# NIRGM_V7.net
KiCad netlist of a schematic drawn in EAGLE
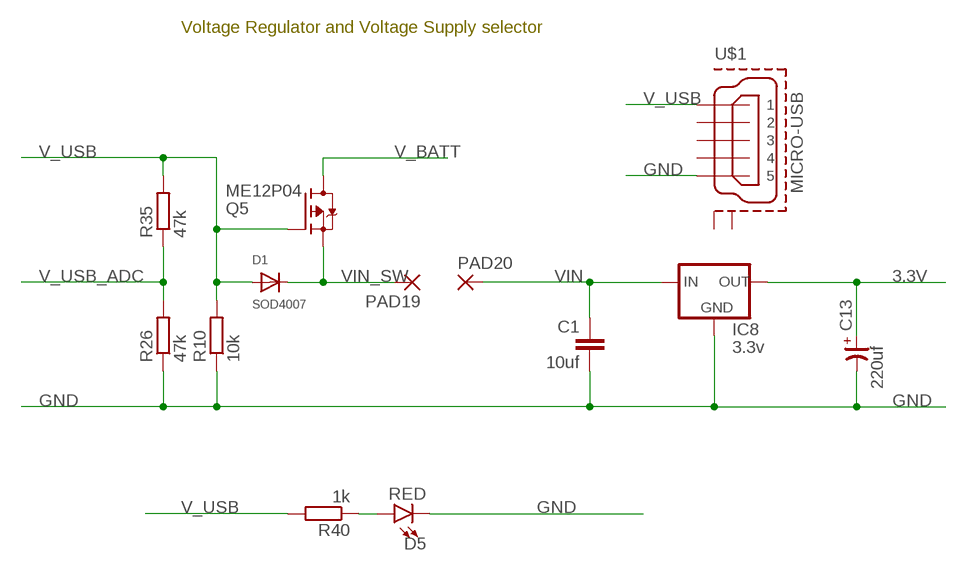
[diagram p0: schematic, sheet 1]
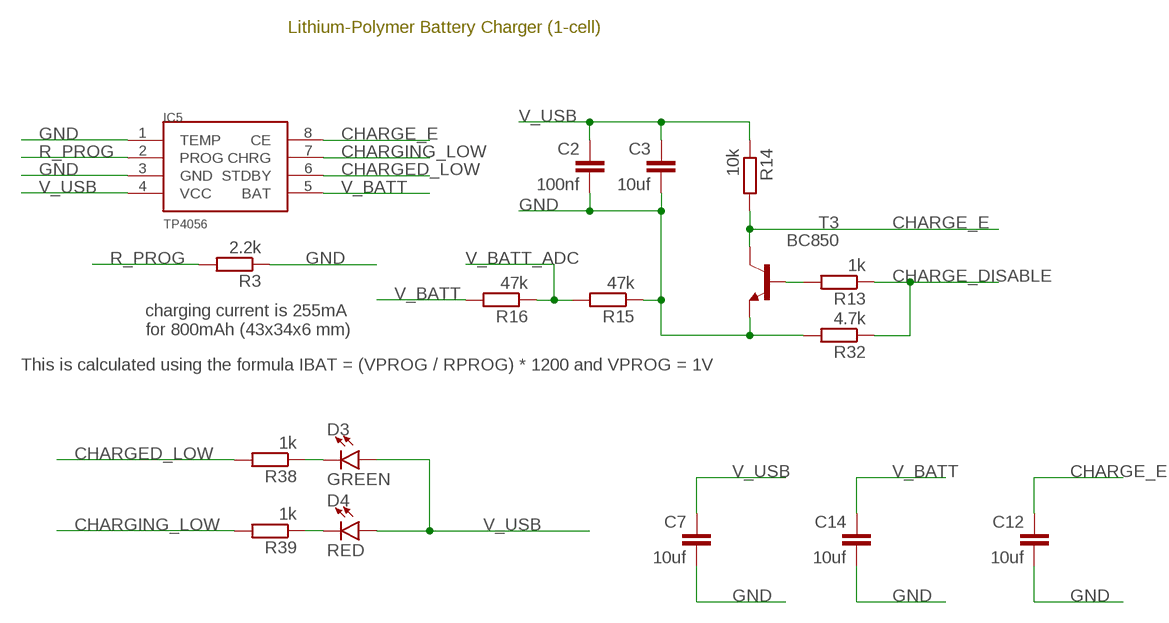
[diagram p1: schematic, sheet 2]
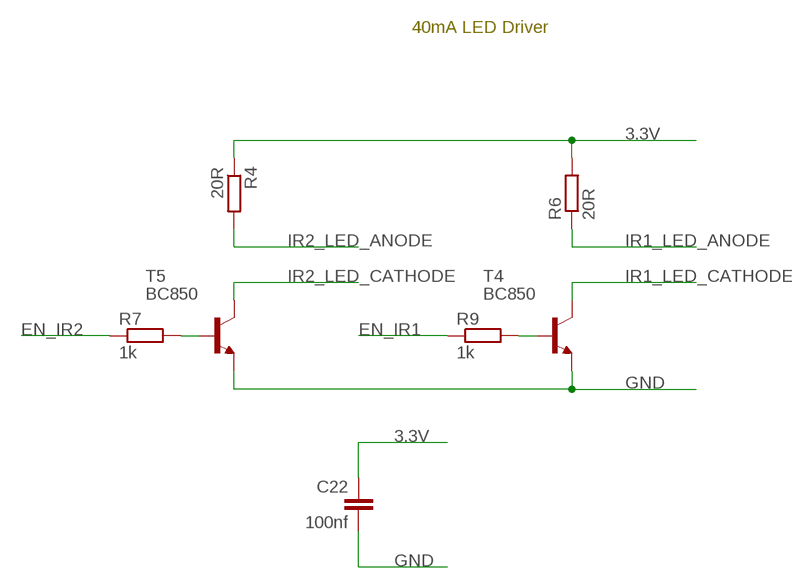
[diagram p2: schematic, sheet 3]
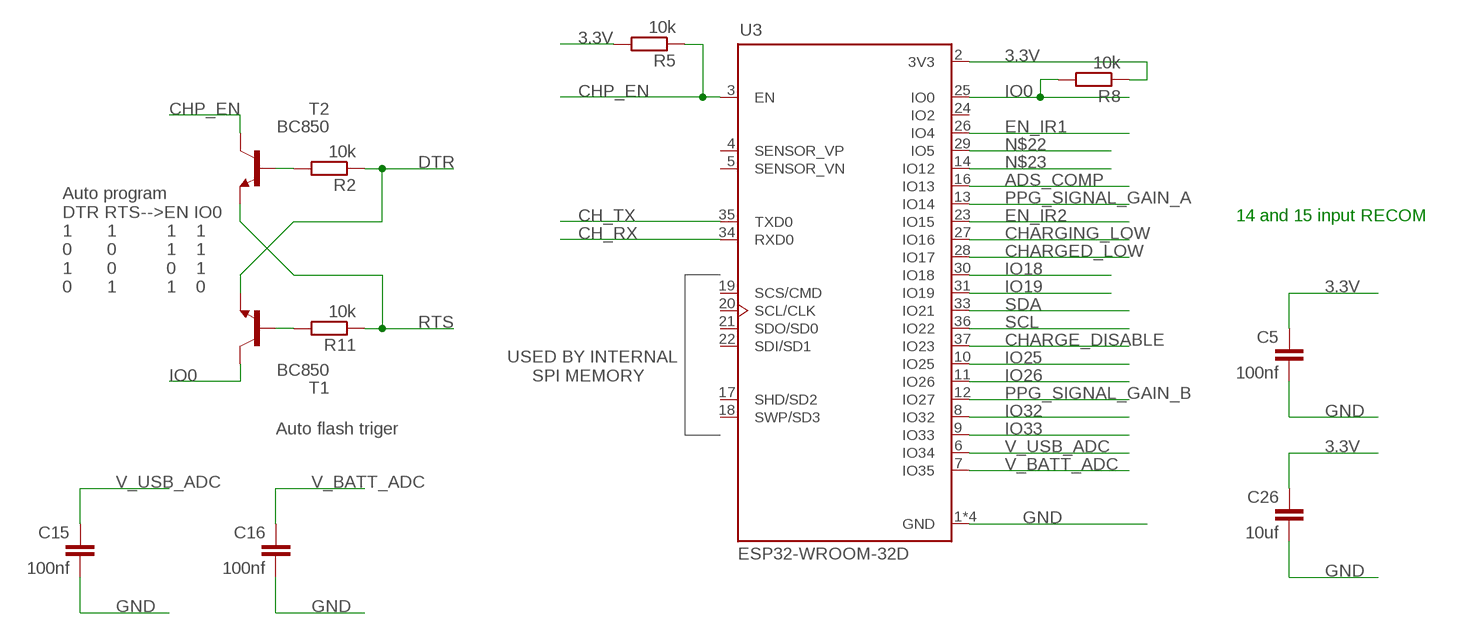
[diagram p3: schematic, sheet 4]
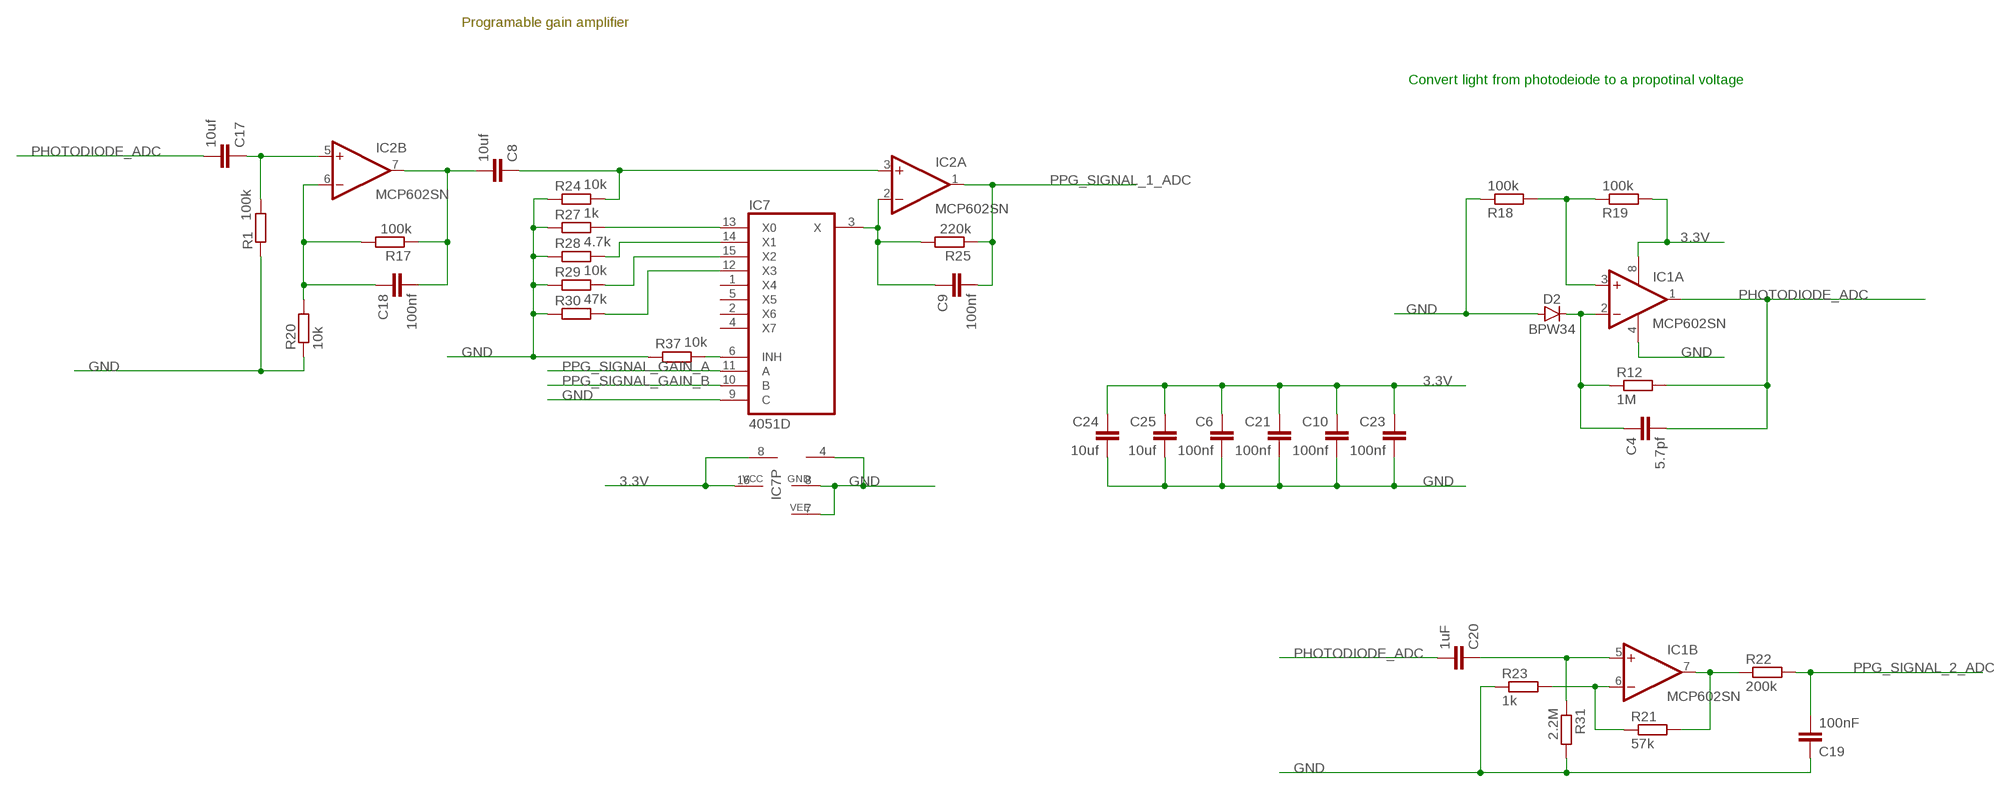
[diagram p4: schematic, sheet 5]
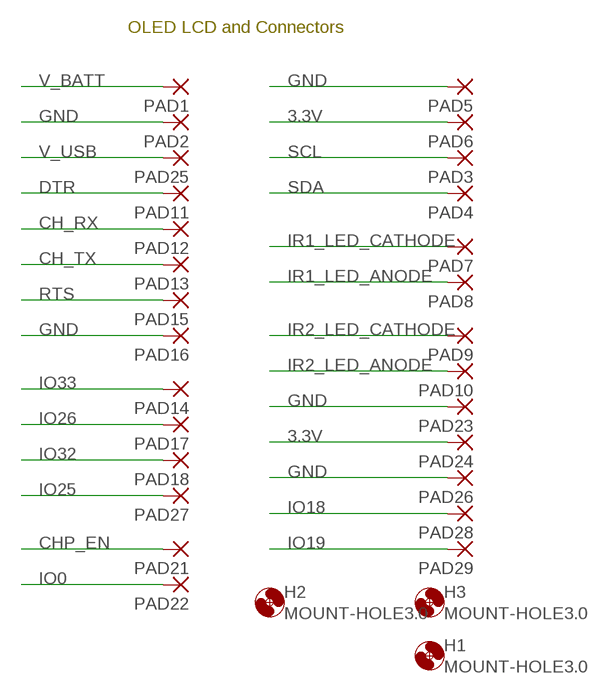
[diagram p5: schematic, sheet 6]
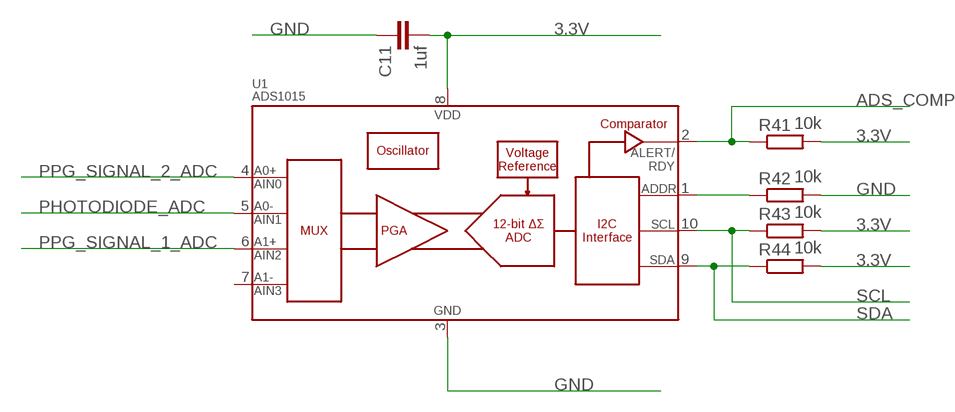
[diagram p6: schematic, sheet 7]

(export (version "E")
  (design (tool "Eeschema 10.0.6"))
  (components
    (comp (ref "H1")
      (value "MOUNT-HOLE3.0")
      (footprint "eagle-import:3,0")
      (libsource (lib "eagle-import") (part "MOUNT-HOLE3.0"))
    )
    (comp (ref "H2")
      (value "MOUNT-HOLE3.0")
      (footprint "eagle-import:3,0")
      (libsource (lib "eagle-import") (part "MOUNT-HOLE3.0"))
    )
    (comp (ref "H3")
      (value "MOUNT-HOLE3.0")
      (footprint "eagle-import:3,0")
      (libsource (lib "eagle-import") (part "MOUNT-HOLE3.0"))
    )
    (comp (ref "PAD1")
      (value "WIREPADSMD5-2,5")
      (footprint "eagle-import:5-2,5")
      (libsource (lib "eagle-import") (part "WIREPADSMD5-2,5"))
    )
    (comp (ref "PAD2")
      (value "WIREPADSMD5-2,5")
      (footprint "eagle-import:5-2,5")
      (libsource (lib "eagle-import") (part "WIREPADSMD5-2,5"))
    )
    (comp (ref "PAD3")
      (value "SMD2")
      (footprint "eagle-import:SMD1,27-2,54")
      (libsource (lib "eagle-import") (part "SMD2"))
    )
    (comp (ref "PAD4")
      (value "SMD2")
      (footprint "eagle-import:SMD1,27-2,54")
      (libsource (lib "eagle-import") (part "SMD2"))
    )
    (comp (ref "PAD5")
      (value "SMD2")
      (footprint "eagle-import:SMD1,27-2,54")
      (libsource (lib "eagle-import") (part "SMD2"))
    )
    (comp (ref "PAD6")
      (value "SMD2")
      (footprint "eagle-import:SMD1,27-2,54")
      (libsource (lib "eagle-import") (part "SMD2"))
    )
    (comp (ref "PAD7")
      (value "SMD2")
      (footprint "eagle-import:SMD1,27-2,54")
      (libsource (lib "eagle-import") (part "SMD2"))
    )
    (comp (ref "PAD8")
      (value "SMD2")
      (footprint "eagle-import:SMD1,27-2,54")
      (libsource (lib "eagle-import") (part "SMD2"))
    )
    (comp (ref "PAD9")
      (value "SMD2")
      (footprint "eagle-import:SMD1,27-2,54")
      (libsource (lib "eagle-import") (part "SMD2"))
    )
    (comp (ref "PAD10")
      (value "SMD2")
      (footprint "eagle-import:SMD1,27-2,54")
      (libsource (lib "eagle-import") (part "SMD2"))
    )
    (comp (ref "PAD11")
      (value "SMD2")
      (footprint "eagle-import:SMD1,27-2,54")
      (libsource (lib "eagle-import") (part "SMD2"))
    )
    (comp (ref "PAD12")
      (value "SMD2")
      (footprint "eagle-import:SMD1,27-2,54")
      (libsource (lib "eagle-import") (part "SMD2"))
    )
    (comp (ref "PAD13")
      (value "SMD2")
      (footprint "eagle-import:SMD1,27-2,54")
      (libsource (lib "eagle-import") (part "SMD2"))
    )
    (comp (ref "PAD14")
      (value "SMD2")
      (footprint "eagle-import:SMD1,27-2,54")
      (libsource (lib "eagle-import") (part "SMD2"))
    )
    (comp (ref "PAD15")
      (value "SMD2")
      (footprint "eagle-import:SMD1,27-2,54")
      (libsource (lib "eagle-import") (part "SMD2"))
    )
    (comp (ref "PAD16")
      (value "SMD2")
      (footprint "eagle-import:SMD1,27-2,54")
      (libsource (lib "eagle-import") (part "SMD2"))
    )
    (comp (ref "PAD17")
      (value "SMD2")
      (footprint "eagle-import:SMD1,27-2,54")
      (libsource (lib "eagle-import") (part "SMD2"))
    )
    (comp (ref "PAD18")
      (value "SMD2")
      (footprint "eagle-import:SMD1,27-2,54")
      (libsource (lib "eagle-import") (part "SMD2"))
    )
    (comp (ref "PAD21")
      (value "SMD2")
      (footprint "eagle-import:SMD1,27-2,54")
      (libsource (lib "eagle-import") (part "SMD2"))
    )
    (comp (ref "PAD22")
      (value "SMD2")
      (footprint "eagle-import:SMD1,27-2,54")
      (libsource (lib "eagle-import") (part "SMD2"))
    )
    (comp (ref "PAD23")
      (value "SMD2")
      (footprint "eagle-import:SMD1,27-2,54")
      (libsource (lib "eagle-import") (part "SMD2"))
    )
    (comp (ref "PAD24")
      (value "SMD2")
      (footprint "eagle-import:SMD1,27-2,54")
      (libsource (lib "eagle-import") (part "SMD2"))
    )
    (comp (ref "PAD25")
      (value "SMD2")
      (footprint "eagle-import:SMD1,27-2,54")
      (libsource (lib "eagle-import") (part "SMD2"))
    )
    (comp (ref "PAD26")
      (value "SMD2")
      (footprint "eagle-import:SMD1,27-2,54")
      (libsource (lib "eagle-import") (part "SMD2"))
    )
    (comp (ref "PAD27")
      (value "SMD2")
      (footprint "eagle-import:SMD1,27-2,54")
      (libsource (lib "eagle-import") (part "SMD2"))
    )
    (comp (ref "PAD28")
      (value "SMD2")
      (footprint "eagle-import:SMD1,27-2,54")
      (libsource (lib "eagle-import") (part "SMD2"))
    )
    (comp (ref "PAD29")
      (value "SMD2")
      (footprint "eagle-import:SMD1,27-2,54")
      (libsource (lib "eagle-import") (part "SMD2"))
    )
    (comp (ref "C2")
      (value "100nf")
      (footprint "eagle-import:C1206K")
      (libsource (lib "eagle-import") (part "C-EUC1206K"))
    )
    (comp (ref "C3")
      (value "10uf")
      (footprint "eagle-import:C1206K")
      (libsource (lib "eagle-import") (part "C-EUC1206K"))
    )
    (comp (ref "C7")
      (value "10uf")
      (footprint "eagle-import:C1206K")
      (libsource (lib "eagle-import") (part "C-EUC1206K"))
    )
    (comp (ref "C12")
      (value "10uf")
      (footprint "eagle-import:C1206K")
      (libsource (lib "eagle-import") (part "C-EUC1206K"))
    )
    (comp (ref "C14")
      (value "10uf")
      (footprint "eagle-import:C1206K")
      (libsource (lib "eagle-import") (part "C-EUC1206K"))
    )
    (comp (ref "D3")
      (value "GREEN")
      (footprint "eagle-import:LED-1206")
      (libsource (lib "eagle-import") (part "LED-GREEN1206"))
    )
    (comp (ref "D4")
      (value "RED")
      (footprint "eagle-import:LED-1206")
      (libsource (lib "eagle-import") (part "LED-GREEN1206"))
    )
    (comp (ref "IC5")
      (value "TP4056")
      (footprint "eagle-import:SOP-8")
      (libsource (lib "eagle-import") (part "TP4056"))
    )
    (comp (ref "R3")
      (value "2.2k")
      (footprint "eagle-import:R1206")
      (libsource (lib "eagle-import") (part "R-EU_R1206"))
    )
    (comp (ref "R13")
      (value "1k")
      (footprint "eagle-import:R1206")
      (libsource (lib "eagle-import") (part "R-EU_R1206"))
    )
    (comp (ref "R14")
      (value "10k")
      (footprint "eagle-import:R1206")
      (libsource (lib "eagle-import") (part "R-EU_R1206"))
    )
    (comp (ref "R15")
      (value "47k")
      (footprint "eagle-import:R1206")
      (libsource (lib "eagle-import") (part "R-EU_R1206"))
    )
    (comp (ref "R16")
      (value "47k")
      (footprint "eagle-import:R1206")
      (libsource (lib "eagle-import") (part "R-EU_R1206"))
    )
    (comp (ref "R32")
      (value "4.7k")
      (footprint "eagle-import:R1206")
      (libsource (lib "eagle-import") (part "R-EU_R1206"))
    )
    (comp (ref "R38")
      (value "1k")
      (footprint "eagle-import:R1206")
      (libsource (lib "eagle-import") (part "R-EU_R1206"))
    )
    (comp (ref "R39")
      (value "1k")
      (footprint "eagle-import:R1206")
      (libsource (lib "eagle-import") (part "R-EU_R1206"))
    )
    (comp (ref "T3")
      (value "BC850")
      (footprint "eagle-import:SOT23")
      (libsource (lib "eagle-import") (part "BC850"))
    )
    (comp (ref "C11")
      (value "1uf")
      (footprint "eagle-import:C1206K")
      (libsource (lib "eagle-import") (part "C-EUC1206K"))
    )
    (comp (ref "R41")
      (value "10k")
      (footprint "eagle-import:R1206")
      (libsource (lib "eagle-import") (part "R-EU_R1206"))
    )
    (comp (ref "R42")
      (value "10k")
      (footprint "eagle-import:R1206")
      (libsource (lib "eagle-import") (part "R-EU_R1206"))
    )
    (comp (ref "R43")
      (value "10k")
      (footprint "eagle-import:R1206")
      (libsource (lib "eagle-import") (part "R-EU_R1206"))
    )
    (comp (ref "R44")
      (value "10k")
      (footprint "eagle-import:R1206")
      (libsource (lib "eagle-import") (part "R-EU_R1206"))
    )
    (comp (ref "U1")
      (value "ADS1015")
      (footprint "eagle-import:MSOP10")
      (libsource (lib "eagle-import") (part "ADS1015"))
    )
    (comp (ref "C1")
      (value "10uf")
      (footprint "eagle-import:C1206K")
      (libsource (lib "eagle-import") (part "C-EUC1206K"))
    )
    (comp (ref "C13")
      (value "220uf")
      (footprint "eagle-import:7343_T")
      (libsource (lib "eagle-import") (part "CP-7343"))
    )
    (comp (ref "D1")
      (value "SOD4007")
      (footprint "eagle-import:SOD-123FL")
      (libsource (lib "eagle-import") (part "DIODE_SOD-123FL"))
    )
    (comp (ref "D5")
      (value "RED")
      (footprint "eagle-import:LED-1206")
      (libsource (lib "eagle-import") (part "LED-GREEN1206"))
    )
    (comp (ref "IC8")
      (value "3.3v")
      (footprint "eagle-import:TO252")
      (libsource (lib "eagle-import") (part "LM1117TO252"))
    )
    (comp (ref "PAD19")
      (value "SMD2")
      (footprint "eagle-import:SMD1,27-2,54")
      (libsource (lib "eagle-import") (part "SMD2"))
    )
    (comp (ref "PAD20")
      (value "SMD2")
      (footprint "eagle-import:SMD1,27-2,54")
      (libsource (lib "eagle-import") (part "SMD2"))
    )
    (comp (ref "Q5")
      (value "ME12P04")
      (footprint "eagle-import:TO252")
      (libsource (lib "eagle-import") (part "FDD4141TO252"))
    )
    (comp (ref "R10")
      (value "10k")
      (footprint "eagle-import:R1206")
      (libsource (lib "eagle-import") (part "R-EU_R1206"))
    )
    (comp (ref "R26")
      (value "47k")
      (footprint "eagle-import:R1206")
      (libsource (lib "eagle-import") (part "R-EU_R1206"))
    )
    (comp (ref "R35")
      (value "47k")
      (footprint "eagle-import:R1206")
      (libsource (lib "eagle-import") (part "R-EU_R1206"))
    )
    (comp (ref "R40")
      (value "1k")
      (footprint "eagle-import:R1206")
      (libsource (lib "eagle-import") (part "R-EU_R1206"))
    )
    (comp (ref "U$1")
      (value "MICRO-USB")
      (footprint "eagle-import:47589-0001")
      (libsource (lib "eagle-import") (part "MICRO-USB-RECEPTACLE47589-0001"))
    )
    (comp (ref "C22")
      (value "100nf")
      (footprint "eagle-import:C1206K")
      (libsource (lib "eagle-import") (part "C-EUC1206K"))
    )
    (comp (ref "R4")
      (value "20R")
      (footprint "eagle-import:R1206")
      (libsource (lib "eagle-import") (part "R-EU_R1206"))
    )
    (comp (ref "R6")
      (value "20R")
      (footprint "eagle-import:R1206")
      (libsource (lib "eagle-import") (part "R-EU_R1206"))
    )
    (comp (ref "R7")
      (value "1k")
      (footprint "eagle-import:R1206")
      (libsource (lib "eagle-import") (part "R-EU_R1206"))
    )
    (comp (ref "R9")
      (value "1k")
      (footprint "eagle-import:R1206")
      (libsource (lib "eagle-import") (part "R-EU_R1206"))
    )
    (comp (ref "T4")
      (value "BC850")
      (footprint "eagle-import:SOT23")
      (libsource (lib "eagle-import") (part "BC850"))
    )
    (comp (ref "T5")
      (value "BC850")
      (footprint "eagle-import:SOT23")
      (libsource (lib "eagle-import") (part "BC850"))
    )
    (comp (ref "C5")
      (value "100nf")
      (footprint "eagle-import:C1206K")
      (libsource (lib "eagle-import") (part "C-EUC1206K"))
    )
    (comp (ref "C15")
      (value "100nf")
      (footprint "eagle-import:C1206K")
      (libsource (lib "eagle-import") (part "C-EUC1206K"))
    )
    (comp (ref "C16")
      (value "100nf")
      (footprint "eagle-import:C1206K")
      (libsource (lib "eagle-import") (part "C-EUC1206K"))
    )
    (comp (ref "C26")
      (value "10uf")
      (footprint "eagle-import:C1206K")
      (libsource (lib "eagle-import") (part "C-EUC1206K"))
    )
    (comp (ref "R2")
      (value "10k")
      (footprint "eagle-import:R1206")
      (libsource (lib "eagle-import") (part "R-EU_R1206"))
    )
    (comp (ref "R5")
      (value "10k")
      (footprint "eagle-import:R1206")
      (libsource (lib "eagle-import") (part "R-EU_R1206"))
    )
    (comp (ref "R8")
      (value "10k")
      (footprint "eagle-import:R1206")
      (libsource (lib "eagle-import") (part "R-EU_R1206"))
    )
    (comp (ref "R11")
      (value "10k")
      (footprint "eagle-import:R1206")
      (libsource (lib "eagle-import") (part "R-EU_R1206"))
    )
    (comp (ref "T1")
      (value "BC850")
      (footprint "eagle-import:SOT23")
      (libsource (lib "eagle-import") (part "BC850"))
    )
    (comp (ref "T2")
      (value "BC850")
      (footprint "eagle-import:SOT23")
      (libsource (lib "eagle-import") (part "BC850"))
    )
    (comp (ref "U3")
      (value "ESP32-WROOM-32D")
      (footprint "eagle-import:MODULE_ESP32-WROOM-32D")
      (fields (field (name "MF") "Espressif Systems"))
      (libsource (lib "eagle-import") (part "ESP32-WROOM-32D"))
    )
    (comp (ref "C4")
      (value "5.7pf")
      (footprint "eagle-import:C1206K")
      (libsource (lib "eagle-import") (part "C-EUC1206K"))
    )
    (comp (ref "C6")
      (value "100nf")
      (footprint "eagle-import:C1206K")
      (libsource (lib "eagle-import") (part "C-EUC1206K"))
    )
    (comp (ref "C8")
      (value "10uf")
      (footprint "eagle-import:C1206K")
      (libsource (lib "eagle-import") (part "C-EUC1206K"))
    )
    (comp (ref "C9")
      (value "100nf")
      (footprint "eagle-import:C1206K")
      (libsource (lib "eagle-import") (part "C-EUC1206K"))
    )
    (comp (ref "C10")
      (value "100nf")
      (footprint "eagle-import:C1206K")
      (libsource (lib "eagle-import") (part "C-EUC1206K"))
    )
    (comp (ref "C17")
      (value "10uf")
      (footprint "eagle-import:C1206K")
      (libsource (lib "eagle-import") (part "C-EUC1206K"))
    )
    (comp (ref "C18")
      (value "100nf")
      (footprint "eagle-import:C1206K")
      (libsource (lib "eagle-import") (part "C-EUC1206K"))
    )
    (comp (ref "C19")
      (value "100nF")
      (footprint "eagle-import:C1206K")
      (libsource (lib "eagle-import") (part "C-EUC1206K"))
    )
    (comp (ref "C20")
      (value "1uF")
      (footprint "eagle-import:C1206K")
      (libsource (lib "eagle-import") (part "C-EUC1206K"))
    )
    (comp (ref "C21")
      (value "100nf")
      (footprint "eagle-import:C1206K")
      (libsource (lib "eagle-import") (part "C-EUC1206K"))
    )
    (comp (ref "C23")
      (value "100nf")
      (footprint "eagle-import:C1206K")
      (libsource (lib "eagle-import") (part "C-EUC1206K"))
    )
    (comp (ref "C24")
      (value "10uf")
      (footprint "eagle-import:C1206K")
      (libsource (lib "eagle-import") (part "C-EUC1206K"))
    )
    (comp (ref "C25")
      (value "10uf")
      (footprint "eagle-import:C1206K")
      (libsource (lib "eagle-import") (part "C-EUC1206K"))
    )
    (comp (ref "D2")
      (value "BPW34")
      (footprint "eagle-import:BPW34")
      (libsource (lib "eagle-import") (part "BPW34"))
    )
    (comp (ref "IC1")
      (value "MCP602SN")
      (footprint "eagle-import:SO08")
      (libsource (lib "eagle-import") (part "linear_262_MCP602SN"))
    )
    (comp (ref "IC2")
      (value "MCP602SN")
      (footprint "eagle-import:SO08")
      (libsource (lib "eagle-import") (part "MCP602SN"))
    )
    (comp (ref "IC7")
      (value "4051D")
      (footprint "eagle-import:SO16")
      (libsource (lib "eagle-import") (part "4051D"))
    )
    (comp (ref "R1")
      (value "100k")
      (footprint "eagle-import:R1206")
      (libsource (lib "eagle-import") (part "R-EU_R1206"))
    )
    (comp (ref "R12")
      (value "1M")
      (footprint "eagle-import:R1206")
      (libsource (lib "eagle-import") (part "R-EU_R1206"))
    )
    (comp (ref "R17")
      (value "100k")
      (footprint "eagle-import:R1206")
      (libsource (lib "eagle-import") (part "R-EU_R1206"))
    )
    (comp (ref "R18")
      (value "100k")
      (footprint "eagle-import:R1206")
      (libsource (lib "eagle-import") (part "R-EU_R1206"))
    )
    (comp (ref "R19")
      (value "100k")
      (footprint "eagle-import:R1206")
      (libsource (lib "eagle-import") (part "R-EU_R1206"))
    )
    (comp (ref "R20")
      (value "10k")
      (footprint "eagle-import:R1206")
      (libsource (lib "eagle-import") (part "R-EU_R1206"))
    )
    (comp (ref "R21")
      (value "57k")
      (footprint "eagle-import:R1206")
      (libsource (lib "eagle-import") (part "R-EU_R1206"))
    )
    (comp (ref "R22")
      (value "200k")
      (footprint "eagle-import:R1206")
      (libsource (lib "eagle-import") (part "R-EU_R1206"))
    )
    (comp (ref "R23")
      (value "1k")
      (footprint "eagle-import:R1206")
      (libsource (lib "eagle-import") (part "R-EU_R1206"))
    )
    (comp (ref "R24")
      (value "10k")
      (footprint "eagle-import:R1206")
      (libsource (lib "eagle-import") (part "R-EU_R1206"))
    )
    (comp (ref "R25")
      (value "220k")
      (footprint "eagle-import:R1206")
      (libsource (lib "eagle-import") (part "R-EU_R1206"))
    )
    (comp (ref "R27")
      (value "1k")
      (footprint "eagle-import:R1206")
      (libsource (lib "eagle-import") (part "R-EU_R1206"))
    )
    (comp (ref "R28")
      (value "4.7k")
      (footprint "eagle-import:R1206")
      (libsource (lib "eagle-import") (part "R-EU_R1206"))
    )
    (comp (ref "R29")
      (value "10k")
      (footprint "eagle-import:R1206")
      (libsource (lib "eagle-import") (part "R-EU_R1206"))
    )
    (comp (ref "R30")
      (value "47k")
      (footprint "eagle-import:R1206")
      (libsource (lib "eagle-import") (part "R-EU_R1206"))
    )
    (comp (ref "R31")
      (value "2.2M")
      (footprint "eagle-import:R1206")
      (libsource (lib "eagle-import") (part "R-EU_R1206"))
    )
    (comp (ref "R37")
      (value "10k")
      (footprint "eagle-import:R1206")
      (libsource (lib "eagle-import") (part "R-EU_R1206"))
    )
  )
  (nets
    (net (code "1") (name "3.3V") (class "Default")
      (node (ref "C10") (pin "1") (pinfunction "1_1") (pintype "passive"))
      (node (ref "C11") (pin "2") (pinfunction "2_2") (pintype "passive"))
      (node (ref "C13") (pin "+") (pinfunction "+_+") (pintype "passive"))
      (node (ref "C21") (pin "1") (pinfunction "1_1") (pintype "passive"))
      (node (ref "C22") (pin "1") (pinfunction "1_1") (pintype "passive"))
      (node (ref "C23") (pin "1") (pinfunction "1_1") (pintype "passive"))
      (node (ref "C24") (pin "1") (pinfunction "1_1") (pintype "passive"))
      (node (ref "C25") (pin "1") (pinfunction "1_1") (pintype "passive"))
      (node (ref "C26") (pin "1") (pinfunction "1_1") (pintype "passive"))
      (node (ref "C5") (pin "1") (pinfunction "1_1") (pintype "passive"))
      (node (ref "C6") (pin "1") (pinfunction "1_1") (pintype "passive"))
      (node (ref "IC1") (pin "8") (pinfunction "V+_8") (pintype "power_in"))
      (node (ref "IC2") (pin "8") (pinfunction "V+_8") (pintype "power_in"))
      (node (ref "IC7") (pin "16") (pinfunction "VCC_16") (pintype "power_in"))
      (node (ref "IC8") (pin "3") (pinfunction "OUT_3") (pintype "passive"))
      (node (ref "PAD24") (pin "1") (pinfunction "P_1") (pintype "passive"))
      (node (ref "PAD6") (pin "1") (pinfunction "P_1") (pintype "passive"))
      (node (ref "R19") (pin "2") (pinfunction "2_2") (pintype "passive"))
      (node (ref "R4") (pin "1") (pinfunction "1_1") (pintype "passive"))
      (node (ref "R41") (pin "2") (pinfunction "2_2") (pintype "passive"))
      (node (ref "R43") (pin "2") (pinfunction "2_2") (pintype "passive"))
      (node (ref "R44") (pin "2") (pinfunction "2_2") (pintype "passive"))
      (node (ref "R5") (pin "2") (pinfunction "2_2") (pintype "passive"))
      (node (ref "R6") (pin "2") (pinfunction "2_2") (pintype "passive"))
      (node (ref "R8") (pin "1") (pinfunction "1_1") (pintype "passive"))
      (node (ref "U1") (pin "8") (pinfunction "VDD_8") (pintype "bidirectional"))
      (node (ref "U3") (pin "2") (pinfunction "3V3_2") (pintype "power_in"))
    )
    (net (code "2") (name "ADS_COMP") (class "Default")
      (node (ref "R41") (pin "1") (pinfunction "1_1") (pintype "passive"))
      (node (ref "U1") (pin "2") (pinfunction "ALERT/RDY_2") (pintype "bidirectional"))
      (node (ref "U3") (pin "16") (pinfunction "IO13_16") (pintype "bidirectional"))
    )
    (net (code "3") (name "CHARGED_LOW") (class "Default")
      (node (ref "IC5") (pin "6") (pinfunction "STDBY_6") (pintype "bidirectional"))
      (node (ref "R38") (pin "2") (pinfunction "2_2") (pintype "passive"))
      (node (ref "U3") (pin "28") (pinfunction "IO17_28") (pintype "bidirectional"))
    )
    (net (code "4") (name "CHARGE_DISABLE") (class "Default")
      (node (ref "R13") (pin "1") (pinfunction "1_1") (pintype "passive"))
      (node (ref "R32") (pin "1") (pinfunction "1_1") (pintype "passive"))
      (node (ref "U3") (pin "37") (pinfunction "IO23_37") (pintype "bidirectional"))
    )
    (net (code "5") (name "CHARGE_E") (class "Default")
      (node (ref "C12") (pin "1") (pinfunction "1_1") (pintype "passive"))
      (node (ref "IC5") (pin "8") (pinfunction "CE_8") (pintype "bidirectional"))
      (node (ref "R14") (pin "2") (pinfunction "2_2") (pintype "passive"))
      (node (ref "T3") (pin "3") (pinfunction "C_3") (pintype "passive"))
    )
    (net (code "6") (name "CHARGING_LOW") (class "Default")
      (node (ref "IC5") (pin "7") (pinfunction "CHRG_7") (pintype "bidirectional"))
      (node (ref "R39") (pin "2") (pinfunction "2_2") (pintype "passive"))
      (node (ref "U3") (pin "27") (pinfunction "IO16_27") (pintype "bidirectional"))
    )
    (net (code "7") (name "CHP_EN") (class "Default")
      (node (ref "PAD21") (pin "1") (pinfunction "P_1") (pintype "passive"))
      (node (ref "R5") (pin "1") (pinfunction "1_1") (pintype "passive"))
      (node (ref "T2") (pin "3") (pinfunction "C_3") (pintype "passive"))
      (node (ref "U3") (pin "3") (pinfunction "EN_3") (pintype "input"))
    )
    (net (code "8") (name "CH_RX") (class "Default")
      (node (ref "PAD12") (pin "1") (pinfunction "P_1") (pintype "passive"))
      (node (ref "U3") (pin "34") (pinfunction "RXD0_34") (pintype "bidirectional"))
    )
    (net (code "9") (name "CH_TX") (class "Default")
      (node (ref "PAD13") (pin "1") (pinfunction "P_1") (pintype "passive"))
      (node (ref "U3") (pin "35") (pinfunction "TXD0_35") (pintype "bidirectional"))
    )
    (net (code "10") (name "DTR") (class "Default")
      (node (ref "PAD11") (pin "1") (pinfunction "P_1") (pintype "passive"))
      (node (ref "R2") (pin "1") (pinfunction "1_1") (pintype "passive"))
      (node (ref "T1") (pin "2") (pinfunction "E_2") (pintype "passive"))
    )
    (net (code "11") (name "EN_IR1") (class "Default")
      (node (ref "R9") (pin "1") (pinfunction "1_1") (pintype "passive"))
      (node (ref "U3") (pin "26") (pinfunction "IO4_26") (pintype "bidirectional"))
    )
    (net (code "12") (name "EN_IR2") (class "Default")
      (node (ref "R7") (pin "1") (pinfunction "1_1") (pintype "passive"))
      (node (ref "U3") (pin "23") (pinfunction "IO15_23") (pintype "bidirectional"))
    )
    (net (code "13") (name "GND") (class "Default")
      (node (ref "C1") (pin "2") (pinfunction "2_2") (pintype "passive"))
      (node (ref "C10") (pin "2") (pinfunction "2_2") (pintype "passive"))
      (node (ref "C11") (pin "1") (pinfunction "1_1") (pintype "passive"))
      (node (ref "C12") (pin "2") (pinfunction "2_2") (pintype "passive"))
      (node (ref "C13") (pin "-") (pinfunction "-_-") (pintype "passive"))
      (node (ref "C14") (pin "2") (pinfunction "2_2") (pintype "passive"))
      (node (ref "C15") (pin "2") (pinfunction "2_2") (pintype "passive"))
      (node (ref "C16") (pin "2") (pinfunction "2_2") (pintype "passive"))
      (node (ref "C19") (pin "1") (pinfunction "1_1") (pintype "passive"))
      (node (ref "C2") (pin "2") (pinfunction "2_2") (pintype "passive"))
      (node (ref "C21") (pin "2") (pinfunction "2_2") (pintype "passive"))
      (node (ref "C22") (pin "2") (pinfunction "2_2") (pintype "passive"))
      (node (ref "C23") (pin "2") (pinfunction "2_2") (pintype "passive"))
      (node (ref "C24") (pin "2") (pinfunction "2_2") (pintype "passive"))
      (node (ref "C25") (pin "2") (pinfunction "2_2") (pintype "passive"))
      (node (ref "C26") (pin "2") (pinfunction "2_2") (pintype "passive"))
      (node (ref "C3") (pin "2") (pinfunction "2_2") (pintype "passive"))
      (node (ref "C5") (pin "2") (pinfunction "2_2") (pintype "passive"))
      (node (ref "C6") (pin "2") (pinfunction "2_2") (pintype "passive"))
      (node (ref "C7") (pin "2") (pinfunction "2_2") (pintype "passive"))
      (node (ref "D2") (pin "P$1") (pinfunction "A_P$1") (pintype "passive"))
      (node (ref "D5") (pin "C") (pinfunction "C_C") (pintype "passive"))
      (node (ref "IC1") (pin "4") (pinfunction "V-_4") (pintype "power_in"))
      (node (ref "IC2") (pin "4") (pinfunction "V-_4") (pintype "power_in"))
      (node (ref "IC5") (pin "1") (pinfunction "TEMP_1") (pintype "bidirectional"))
      (node (ref "IC5") (pin "3") (pinfunction "GND_3") (pintype "bidirectional"))
      (node (ref "IC7") (pin "7") (pinfunction "VEE_7") (pintype "power_in"))
      (node (ref "IC7") (pin "8") (pinfunction "GND_8") (pintype "power_in"))
      (node (ref "IC7") (pin "9") (pinfunction "C_9") (pintype "input"))
      (node (ref "IC8") (pin "1") (pinfunction "GND_1") (pintype "input"))
      (node (ref "PAD16") (pin "1") (pinfunction "P_1") (pintype "passive"))
      (node (ref "PAD2") (pin "1") (pinfunction "P_1") (pintype "passive"))
      (node (ref "PAD23") (pin "1") (pinfunction "P_1") (pintype "passive"))
      (node (ref "PAD26") (pin "1") (pinfunction "P_1") (pintype "passive"))
      (node (ref "PAD5") (pin "1") (pinfunction "P_1") (pintype "passive"))
      (node (ref "R1") (pin "1") (pinfunction "1_1") (pintype "passive"))
      (node (ref "R10") (pin "1") (pinfunction "1_1") (pintype "passive"))
      (node (ref "R15") (pin "1") (pinfunction "1_1") (pintype "passive"))
      (node (ref "R18") (pin "1") (pinfunction "1_1") (pintype "passive"))
      (node (ref "R20") (pin "1") (pinfunction "1_1") (pintype "passive"))
      (node (ref "R23") (pin "1") (pinfunction "1_1") (pintype "passive"))
      (node (ref "R24") (pin "1") (pinfunction "1_1") (pintype "passive"))
      (node (ref "R26") (pin "1") (pinfunction "1_1") (pintype "passive"))
      (node (ref "R27") (pin "1") (pinfunction "1_1") (pintype "passive"))
      (node (ref "R28") (pin "1") (pinfunction "1_1") (pintype "passive"))
      (node (ref "R29") (pin "1") (pinfunction "1_1") (pintype "passive"))
      (node (ref "R3") (pin "1") (pinfunction "1_1") (pintype "passive"))
      (node (ref "R30") (pin "1") (pinfunction "1_1") (pintype "passive"))
      (node (ref "R31") (pin "2") (pinfunction "2_2") (pintype "passive"))
      (node (ref "R32") (pin "2") (pinfunction "2_2") (pintype "passive"))
      (node (ref "R37") (pin "1") (pinfunction "1_1") (pintype "passive"))
      (node (ref "R42") (pin "2") (pinfunction "2_2") (pintype "passive"))
      (node (ref "T3") (pin "2") (pinfunction "E_2") (pintype "passive"))
      (node (ref "T4") (pin "2") (pinfunction "E_2") (pintype "passive"))
      (node (ref "T5") (pin "2") (pinfunction "E_2") (pintype "passive"))
      (node (ref "U$1") (pin "5") (pinfunction "5_5") (pintype "input"))
      (node (ref "U1") (pin "3") (pinfunction "VSS_3") (pintype "bidirectional"))
      (node (ref "U3") (pin "1") (pinfunction "GND_1") (pintype "power_in"))
      (node (ref "U3") (pin "15") (pinfunction "GND_15") (pintype "power_in"))
      (node (ref "U3") (pin "38") (pinfunction "GND_38") (pintype "power_in"))
      (node (ref "U3") (pin "39") (pinfunction "GND_39") (pintype "power_in"))
    )
    (net (code "14") (name "IO0") (class "Default")
      (node (ref "PAD22") (pin "1") (pinfunction "P_1") (pintype "passive"))
      (node (ref "R8") (pin "2") (pinfunction "2_2") (pintype "passive"))
      (node (ref "T1") (pin "3") (pinfunction "C_3") (pintype "passive"))
      (node (ref "U3") (pin "25") (pinfunction "IO0_25") (pintype "bidirectional"))
    )
    (net (code "15") (name "IO18") (class "Default")
      (node (ref "PAD28") (pin "1") (pinfunction "P_1") (pintype "passive"))
      (node (ref "U3") (pin "30") (pinfunction "IO18_30") (pintype "bidirectional"))
    )
    (net (code "16") (name "IO19") (class "Default")
      (node (ref "PAD29") (pin "1") (pinfunction "P_1") (pintype "passive"))
      (node (ref "U3") (pin "31") (pinfunction "IO19_31") (pintype "bidirectional"))
    )
    (net (code "17") (name "IO25") (class "Default")
      (node (ref "PAD27") (pin "1") (pinfunction "P_1") (pintype "passive"))
      (node (ref "U3") (pin "10") (pinfunction "IO25_10") (pintype "bidirectional"))
    )
    (net (code "18") (name "IO26") (class "Default")
      (node (ref "PAD17") (pin "1") (pinfunction "P_1") (pintype "passive"))
      (node (ref "U3") (pin "11") (pinfunction "IO26_11") (pintype "bidirectional"))
    )
    (net (code "19") (name "IO32") (class "Default")
      (node (ref "PAD18") (pin "1") (pinfunction "P_1") (pintype "passive"))
      (node (ref "U3") (pin "8") (pinfunction "IO32_8") (pintype "bidirectional"))
    )
    (net (code "20") (name "IO33") (class "Default")
      (node (ref "PAD14") (pin "1") (pinfunction "P_1") (pintype "passive"))
      (node (ref "U3") (pin "9") (pinfunction "IO33_9") (pintype "bidirectional"))
    )
    (net (code "21") (name "IR1_LED_ANODE") (class "Default")
      (node (ref "PAD8") (pin "1") (pinfunction "P_1") (pintype "passive"))
      (node (ref "R6") (pin "1") (pinfunction "1_1") (pintype "passive"))
    )
    (net (code "22") (name "IR1_LED_CATHODE") (class "Default")
      (node (ref "PAD7") (pin "1") (pinfunction "P_1") (pintype "passive"))
      (node (ref "T4") (pin "3") (pinfunction "C_3") (pintype "passive"))
    )
    (net (code "23") (name "IR2_LED_ANODE") (class "Default")
      (node (ref "PAD10") (pin "1") (pinfunction "P_1") (pintype "passive"))
      (node (ref "R4") (pin "2") (pinfunction "2_2") (pintype "passive"))
    )
    (net (code "24") (name "IR2_LED_CATHODE") (class "Default")
      (node (ref "PAD9") (pin "1") (pinfunction "P_1") (pintype "passive"))
      (node (ref "T5") (pin "3") (pinfunction "C_3") (pintype "passive"))
    )
    (net (code "25") (name "N$22") (class "Default")
      (node (ref "U3") (pin "29") (pinfunction "IO5_29") (pintype "bidirectional"))
    )
    (net (code "26") (name "N$23") (class "Default")
      (node (ref "U3") (pin "14") (pinfunction "IO12_14") (pintype "bidirectional"))
    )
    (net (code "27") (name "Net-(D2-C)") (class "Default")
      (node (ref "C4") (pin "1") (pinfunction "1_1") (pintype "passive"))
      (node (ref "D2") (pin "P$2") (pinfunction "C_P$2") (pintype "passive"))
      (node (ref "IC1") (pin "2") (pinfunction "-IN_2") (pintype "input"))
      (node (ref "R12") (pin "1") (pinfunction "1_1") (pintype "passive"))
    )
    (net (code "28") (name "Net-(D3-PadC)") (class "Default")
      (node (ref "D3") (pin "C") (pinfunction "C_C") (pintype "passive"))
      (node (ref "R38") (pin "1") (pinfunction "1_1") (pintype "passive"))
    )
    (net (code "29") (name "Net-(D4-PadC)") (class "Default")
      (node (ref "D4") (pin "C") (pinfunction "C_C") (pintype "passive"))
      (node (ref "R39") (pin "1") (pinfunction "1_1") (pintype "passive"))
    )
    (net (code "30") (name "Net-(D5-PadA)") (class "Default")
      (node (ref "D5") (pin "A") (pinfunction "A_A") (pintype "passive"))
      (node (ref "R40") (pin "1") (pinfunction "1_1") (pintype "passive"))
    )
    (net (code "31") (name "Net-(IC1A-+IN)") (class "Default")
      (node (ref "IC1") (pin "3") (pinfunction "+IN_3") (pintype "input"))
      (node (ref "R18") (pin "2") (pinfunction "2_2") (pintype "passive"))
      (node (ref "R19") (pin "1") (pinfunction "1_1") (pintype "passive"))
    )
    (net (code "32") (name "Net-(IC1B-+IN)") (class "Default")
      (node (ref "C20") (pin "1") (pinfunction "1_1") (pintype "passive"))
      (node (ref "IC1") (pin "5") (pinfunction "+IN_5") (pintype "input"))
      (node (ref "R31") (pin "1") (pinfunction "1_1") (pintype "passive"))
    )
    (net (code "33") (name "Net-(IC1B--IN)") (class "Default")
      (node (ref "IC1") (pin "6") (pinfunction "-IN_6") (pintype "input"))
      (node (ref "R21") (pin "1") (pinfunction "1_1") (pintype "passive"))
      (node (ref "R23") (pin "2") (pinfunction "2_2") (pintype "passive"))
    )
    (net (code "34") (name "Net-(IC1B-OUT)") (class "Default")
      (node (ref "IC1") (pin "7") (pinfunction "OUT_7") (pintype "output"))
      (node (ref "R21") (pin "2") (pinfunction "2_2") (pintype "passive"))
      (node (ref "R22") (pin "1") (pinfunction "1_1") (pintype "passive"))
    )
    (net (code "35") (name "Net-(IC2A-+IN)") (class "Default")
      (node (ref "C8") (pin "1") (pinfunction "1_1") (pintype "passive"))
      (node (ref "IC2") (pin "3") (pinfunction "+IN_3") (pintype "input"))
      (node (ref "R24") (pin "2") (pinfunction "2_2") (pintype "passive"))
    )
    (net (code "36") (name "Net-(IC2A--IN)") (class "Default")
      (node (ref "C9") (pin "1") (pinfunction "1_1") (pintype "passive"))
      (node (ref "IC2") (pin "2") (pinfunction "-IN_2") (pintype "input"))
      (node (ref "IC7") (pin "3") (pinfunction "X_3") (pintype "bidirectional"))
      (node (ref "R25") (pin "2") (pinfunction "2_2") (pintype "passive"))
    )
    (net (code "37") (name "Net-(IC2B-+IN)") (class "Default")
      (node (ref "C17") (pin "1") (pinfunction "1_1") (pintype "passive"))
      (node (ref "IC2") (pin "5") (pinfunction "+IN_5") (pintype "input"))
      (node (ref "R1") (pin "2") (pinfunction "2_2") (pintype "passive"))
    )
    (net (code "38") (name "Net-(IC2B--IN)") (class "Default")
      (node (ref "C18") (pin "1") (pinfunction "1_1") (pintype "passive"))
      (node (ref "IC2") (pin "6") (pinfunction "-IN_6") (pintype "input"))
      (node (ref "R17") (pin "2") (pinfunction "2_2") (pintype "passive"))
      (node (ref "R20") (pin "2") (pinfunction "2_2") (pintype "passive"))
    )
    (net (code "39") (name "Net-(IC2B-OUT)") (class "Default")
      (node (ref "C18") (pin "2") (pinfunction "2_2") (pintype "passive"))
      (node (ref "C8") (pin "2") (pinfunction "2_2") (pintype "passive"))
      (node (ref "IC2") (pin "7") (pinfunction "OUT_7") (pintype "output"))
      (node (ref "R17") (pin "1") (pinfunction "1_1") (pintype "passive"))
    )
    (net (code "40") (name "Net-(IC7A-INH)") (class "Default")
      (node (ref "IC7") (pin "6") (pinfunction "INH_6") (pintype "input"))
      (node (ref "R37") (pin "2") (pinfunction "2_2") (pintype "passive"))
    )
    (net (code "41") (name "Net-(IC7A-X0)") (class "Default")
      (node (ref "IC7") (pin "13") (pinfunction "X0_13") (pintype "bidirectional"))
      (node (ref "R27") (pin "2") (pinfunction "2_2") (pintype "passive"))
    )
    (net (code "42") (name "Net-(IC7A-X1)") (class "Default")
      (node (ref "IC7") (pin "14") (pinfunction "X1_14") (pintype "bidirectional"))
      (node (ref "R28") (pin "2") (pinfunction "2_2") (pintype "passive"))
    )
    (net (code "43") (name "Net-(IC7A-X2)") (class "Default")
      (node (ref "IC7") (pin "15") (pinfunction "X2_15") (pintype "bidirectional"))
      (node (ref "R29") (pin "2") (pinfunction "2_2") (pintype "passive"))
    )
    (net (code "44") (name "Net-(IC7A-X3)") (class "Default")
      (node (ref "IC7") (pin "12") (pinfunction "X3_12") (pintype "bidirectional"))
      (node (ref "R30") (pin "2") (pinfunction "2_2") (pintype "passive"))
    )
    (net (code "45") (name "Net-(T1-B)") (class "Default")
      (node (ref "R11") (pin "2") (pinfunction "2_2") (pintype "passive"))
      (node (ref "T1") (pin "1") (pinfunction "B_1") (pintype "passive"))
    )
    (net (code "46") (name "Net-(T2-B)") (class "Default")
      (node (ref "R2") (pin "2") (pinfunction "2_2") (pintype "passive"))
      (node (ref "T2") (pin "1") (pinfunction "B_1") (pintype "passive"))
    )
    (net (code "47") (name "Net-(T3-B)") (class "Default")
      (node (ref "R13") (pin "2") (pinfunction "2_2") (pintype "passive"))
      (node (ref "T3") (pin "1") (pinfunction "B_1") (pintype "passive"))
    )
    (net (code "48") (name "Net-(T4-B)") (class "Default")
      (node (ref "R9") (pin "2") (pinfunction "2_2") (pintype "passive"))
      (node (ref "T4") (pin "1") (pinfunction "B_1") (pintype "passive"))
    )
    (net (code "49") (name "Net-(T5-B)") (class "Default")
      (node (ref "R7") (pin "2") (pinfunction "2_2") (pintype "passive"))
      (node (ref "T5") (pin "1") (pinfunction "B_1") (pintype "passive"))
    )
    (net (code "50") (name "Net-(U1-ADDR)") (class "Default")
      (node (ref "R42") (pin "1") (pinfunction "1_1") (pintype "passive"))
      (node (ref "U1") (pin "1") (pinfunction "ADDR_1") (pintype "bidirectional"))
    )
    (net (code "51") (name "PHOTODIODE_ADC") (class "Default")
      (node (ref "C17") (pin "2") (pinfunction "2_2") (pintype "passive"))
      (node (ref "C20") (pin "2") (pinfunction "2_2") (pintype "passive"))
      (node (ref "C4") (pin "2") (pinfunction "2_2") (pintype "passive"))
      (node (ref "IC1") (pin "1") (pinfunction "OUT_1") (pintype "output"))
      (node (ref "R12") (pin "2") (pinfunction "2_2") (pintype "passive"))
      (node (ref "U1") (pin "5") (pinfunction "AIN1_5") (pintype "bidirectional"))
    )
    (net (code "52") (name "PPG_SIGNAL_1_ADC") (class "Default")
      (node (ref "C9") (pin "2") (pinfunction "2_2") (pintype "passive"))
      (node (ref "IC2") (pin "1") (pinfunction "OUT_1") (pintype "output"))
      (node (ref "R25") (pin "1") (pinfunction "1_1") (pintype "passive"))
      (node (ref "U1") (pin "6") (pinfunction "AIN2_6") (pintype "bidirectional"))
    )
    (net (code "53") (name "PPG_SIGNAL_2_ADC") (class "Default")
      (node (ref "C19") (pin "2") (pinfunction "2_2") (pintype "passive"))
      (node (ref "R22") (pin "2") (pinfunction "2_2") (pintype "passive"))
      (node (ref "U1") (pin "4") (pinfunction "AIN0_4") (pintype "bidirectional"))
    )
    (net (code "54") (name "PPG_SIGNAL_GAIN_A") (class "Default")
      (node (ref "IC7") (pin "11") (pinfunction "A_11") (pintype "input"))
      (node (ref "U3") (pin "13") (pinfunction "IO14_13") (pintype "bidirectional"))
    )
    (net (code "55") (name "PPG_SIGNAL_GAIN_B") (class "Default")
      (node (ref "IC7") (pin "10") (pinfunction "B_10") (pintype "input"))
      (node (ref "U3") (pin "12") (pinfunction "IO27_12") (pintype "bidirectional"))
    )
    (net (code "56") (name "RTS") (class "Default")
      (node (ref "PAD15") (pin "1") (pinfunction "P_1") (pintype "passive"))
      (node (ref "R11") (pin "1") (pinfunction "1_1") (pintype "passive"))
      (node (ref "T2") (pin "2") (pinfunction "E_2") (pintype "passive"))
    )
    (net (code "57") (name "R_PROG") (class "Default")
      (node (ref "IC5") (pin "2") (pinfunction "PROG_2") (pintype "bidirectional"))
      (node (ref "R3") (pin "2") (pinfunction "2_2") (pintype "passive"))
    )
    (net (code "58") (name "SCL") (class "Default")
      (node (ref "PAD3") (pin "1") (pinfunction "P_1") (pintype "passive"))
      (node (ref "R43") (pin "1") (pinfunction "1_1") (pintype "passive"))
      (node (ref "U1") (pin "10") (pinfunction "SCL_10") (pintype "bidirectional"))
      (node (ref "U3") (pin "36") (pinfunction "IO22_36") (pintype "bidirectional"))
    )
    (net (code "59") (name "SDA") (class "Default")
      (node (ref "PAD4") (pin "1") (pinfunction "P_1") (pintype "passive"))
      (node (ref "R44") (pin "1") (pinfunction "1_1") (pintype "passive"))
      (node (ref "U1") (pin "9") (pinfunction "SDA_9") (pintype "bidirectional"))
      (node (ref "U3") (pin "33") (pinfunction "IO21_33") (pintype "bidirectional"))
    )
    (net (code "60") (name "VIN") (class "Default")
      (node (ref "C1") (pin "1") (pinfunction "1_1") (pintype "passive"))
      (node (ref "IC8") (pin "2") (pinfunction "IN_2") (pintype "input"))
      (node (ref "PAD20") (pin "1") (pinfunction "P_1") (pintype "passive"))
    )
    (net (code "61") (name "VIN_SW") (class "Default")
      (node (ref "D1") (pin "C") (pinfunction "C_C") (pintype "passive"))
      (node (ref "PAD19") (pin "1") (pinfunction "P_1") (pintype "passive"))
      (node (ref "Q5") (pin "2") (pinfunction "S_2") (pintype "passive"))
    )
    (net (code "62") (name "V_BATT") (class "Default")
      (node (ref "C14") (pin "1") (pinfunction "1_1") (pintype "passive"))
      (node (ref "IC5") (pin "5") (pinfunction "BAT_5") (pintype "bidirectional"))
      (node (ref "PAD1") (pin "1") (pinfunction "P_1") (pintype "passive"))
      (node (ref "Q5") (pin "3") (pinfunction "D_3") (pintype "passive"))
      (node (ref "R16") (pin "2") (pinfunction "2_2") (pintype "passive"))
    )
    (net (code "63") (name "V_BATT_ADC") (class "Default")
      (node (ref "C16") (pin "1") (pinfunction "1_1") (pintype "passive"))
      (node (ref "R15") (pin "2") (pinfunction "2_2") (pintype "passive"))
      (node (ref "R16") (pin "1") (pinfunction "1_1") (pintype "passive"))
      (node (ref "U3") (pin "7") (pinfunction "IO35_7") (pintype "bidirectional"))
    )
    (net (code "64") (name "V_USB") (class "Default")
      (node (ref "C2") (pin "1") (pinfunction "1_1") (pintype "passive"))
      (node (ref "C3") (pin "1") (pinfunction "1_1") (pintype "passive"))
      (node (ref "C7") (pin "1") (pinfunction "1_1") (pintype "passive"))
      (node (ref "D1") (pin "A") (pinfunction "A_A") (pintype "passive"))
      (node (ref "D3") (pin "A") (pinfunction "A_A") (pintype "passive"))
      (node (ref "D4") (pin "A") (pinfunction "A_A") (pintype "passive"))
      (node (ref "IC5") (pin "4") (pinfunction "VCC_4") (pintype "bidirectional"))
      (node (ref "PAD25") (pin "1") (pinfunction "P_1") (pintype "passive"))
      (node (ref "Q5") (pin "1") (pinfunction "G_1") (pintype "passive"))
      (node (ref "R10") (pin "2") (pinfunction "2_2") (pintype "passive"))
      (node (ref "R14") (pin "1") (pinfunction "1_1") (pintype "passive"))
      (node (ref "R35") (pin "2") (pinfunction "2_2") (pintype "passive"))
      (node (ref "R40") (pin "2") (pinfunction "2_2") (pintype "passive"))
      (node (ref "U$1") (pin "1") (pinfunction "1_1") (pintype "input"))
    )
    (net (code "65") (name "V_USB_ADC") (class "Default")
      (node (ref "C15") (pin "1") (pinfunction "1_1") (pintype "passive"))
      (node (ref "R26") (pin "2") (pinfunction "2_2") (pintype "passive"))
      (node (ref "R35") (pin "1") (pinfunction "1_1") (pintype "passive"))
      (node (ref "U3") (pin "6") (pinfunction "IO34_6") (pintype "bidirectional"))
    )
    (net (code "66") (name "unconnected-(IC7A-X4-Pad1)") (class "Default")
      (node (ref "IC7") (pin "1") (pinfunction "X4_1") (pintype "bidirectional"))
    )
    (net (code "67") (name "unconnected-(IC7A-X5-Pad5)") (class "Default")
      (node (ref "IC7") (pin "5") (pinfunction "X5_5") (pintype "bidirectional"))
    )
    (net (code "68") (name "unconnected-(IC7A-X6-Pad2)") (class "Default")
      (node (ref "IC7") (pin "2") (pinfunction "X6_2") (pintype "bidirectional"))
    )
    (net (code "69") (name "unconnected-(IC7A-X7-Pad4)") (class "Default")
      (node (ref "IC7") (pin "4") (pinfunction "X7_4") (pintype "bidirectional"))
    )
    (net (code "70") (name "unconnected-(U$1-GND1-PadP$1)") (class "Default")
      (node (ref "U$1") (pin "P$1") (pinfunction "GND1_P$1") (pintype "bidirectional"))
    )
    (net (code "71") (name "unconnected-(U$1-GND2-PadP$2)") (class "Default")
      (node (ref "U$1") (pin "P$2") (pinfunction "GND2_P$2") (pintype "bidirectional"))
    )
    (net (code "72") (name "unconnected-(U$1-Pad2)") (class "Default")
      (node (ref "U$1") (pin "2") (pinfunction "2_2") (pintype "input"))
    )
    (net (code "73") (name "unconnected-(U$1-Pad3)") (class "Default")
      (node (ref "U$1") (pin "3") (pinfunction "3_3") (pintype "input"))
    )
    (net (code "74") (name "unconnected-(U$1-Pad4)") (class "Default")
      (node (ref "U$1") (pin "4") (pinfunction "4_4") (pintype "input"))
    )
    (net (code "75") (name "unconnected-(U1-AIN3-Pad7)") (class "Default")
      (node (ref "U1") (pin "7") (pinfunction "AIN3_7") (pintype "bidirectional"))
    )
    (net (code "76") (name "unconnected-(U3-IO2-Pad24)") (class "Default")
      (node (ref "U3") (pin "24") (pinfunction "IO2_24") (pintype "bidirectional"))
    )
    (net (code "77") (name "unconnected-(U3-SCL{slash}CLK-Pad20)") (class "Default")
      (node (ref "U3") (pin "20") (pinfunction "SCL/CLK_20") (pintype "bidirectional"))
    )
    (net (code "78") (name "unconnected-(U3-SCS{slash}CMD-Pad19)") (class "Default")
      (node (ref "U3") (pin "19") (pinfunction "SCS/CMD_19") (pintype "bidirectional"))
    )
    (net (code "79") (name "unconnected-(U3-SDI{slash}SD1-Pad22)") (class "Default")
      (node (ref "U3") (pin "22") (pinfunction "SDI/SD1_22") (pintype "bidirectional"))
    )
    (net (code "80") (name "unconnected-(U3-SDO{slash}SD0-Pad21)") (class "Default")
      (node (ref "U3") (pin "21") (pinfunction "SDO/SD0_21") (pintype "bidirectional"))
    )
    (net (code "81") (name "unconnected-(U3-SENSOR_VN-Pad5)") (class "Default")
      (node (ref "U3") (pin "5") (pinfunction "SENSOR_VN_5") (pintype "input"))
    )
    (net (code "82") (name "unconnected-(U3-SENSOR_VP-Pad4)") (class "Default")
      (node (ref "U3") (pin "4") (pinfunction "SENSOR_VP_4") (pintype "input"))
    )
    (net (code "83") (name "unconnected-(U3-SHD{slash}SD2-Pad17)") (class "Default")
      (node (ref "U3") (pin "17") (pinfunction "SHD/SD2_17") (pintype "bidirectional"))
    )
    (net (code "84") (name "unconnected-(U3-SWP{slash}SD3-Pad18)") (class "Default")
      (node (ref "U3") (pin "18") (pinfunction "SWP/SD3_18") (pintype "bidirectional"))
    )
  )
)
